# Expanders.net
KiCad netlist of a schematic drawn in Altium Designer
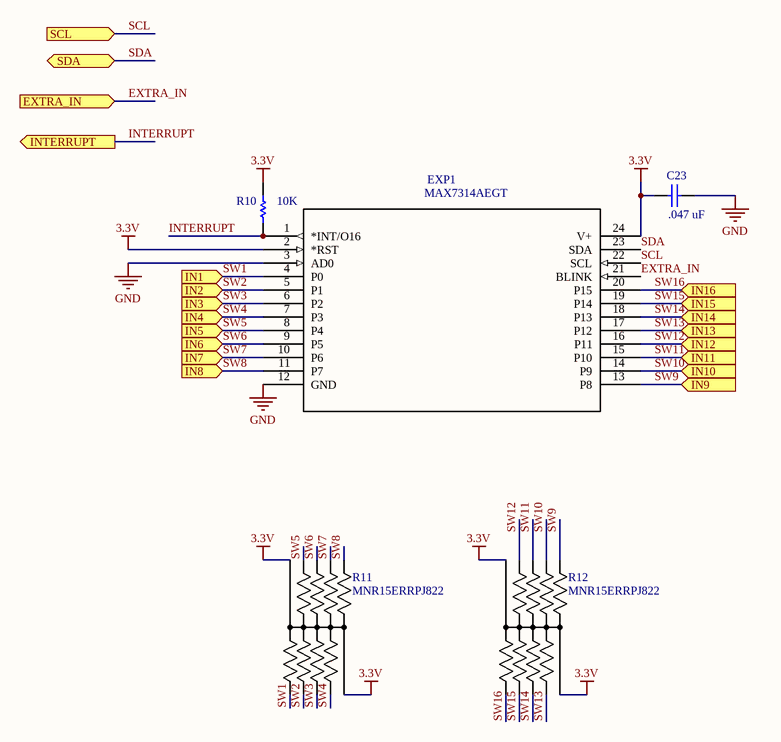
[diagram p0: Expanders.SchDoc]

(export (version "E")
  (design (tool "Eeschema 10.0.6"))
  (components
    (comp (ref "C23")
      (value ".047 uF")
      (footprint "RAD-0.1")
      (description "Capacitor")
      (fields (field (name "Comment") "Cap") (field (name "PUBLISHER") "Altium Limited"))
      (libsource (lib "Miscellaneous Devices") (part "Cap"))
    )
    (comp (ref "EXP1")
      (value "MAX7314AEGT")
      (footprint "21-0055H_24")
      (description "Interface IC - I/O extensions Maxim Integrated MAX7314AEG%2B PWM I%C2%B2C 400 kHz QSOP 24")
      (fields (field (name "MP") "MAX7314AEG+") (field (name "MF") "Maxim Integrated"))
      (libsource (lib "MAX7314AEGT") (part "MAX7314AEGT"))
    )
    (comp (ref "R10")
      (value "10K")
      (footprint "6-0805_N")
      (description "Resistor")
      (fields (field (name "Comment") "R5") (field (name "PUBLISHER") "Altium Limited"))
      (libsource (lib "Miscellaneous Devices") (part "Res1"))
    )
    (comp (ref "R11")
      (value "MNR15ERRPJ822")
      (footprint "MNR15")
      (description "Imported")
      (libsource (lib "surfacemountresarray") (part "MNR15ERRPJ822"))
    )
    (comp (ref "R12")
      (value "MNR15ERRPJ822")
      (footprint "MNR15")
      (description "Imported")
      (libsource (lib "surfacemountresarray") (part "MNR15ERRPJ822"))
    )
  )
  (nets
    (net (code "1") (name "/EXTRA_IN") (class "Default")
      (node (ref "EXP1") (pin "21") (pinfunction "BLINK_21") (pintype "input"))
    )
    (net (code "2") (name "/INTERRUPT") (class "Default")
      (node (ref "EXP1") (pin "1") (pinfunction "*INT/O16_1") (pintype "output"))
      (node (ref "R10") (pin "1") (pinfunction "1_1") (pintype "passive"))
    )
    (net (code "3") (name "/SCL") (class "Default")
      (node (ref "EXP1") (pin "22") (pinfunction "SCL_22") (pintype "input"))
    )
    (net (code "4") (name "/SDA") (class "Default")
      (node (ref "EXP1") (pin "23") (pinfunction "SDA_23") (pintype "passive"))
    )
    (net (code "5") (name "/SW1") (class "Default")
      (node (ref "EXP1") (pin "4") (pinfunction "P0_4") (pintype "passive"))
      (node (ref "R11") (pin "1") (pinfunction "1_1") (pintype "passive"))
    )
    (net (code "6") (name "/SW2") (class "Default")
      (node (ref "EXP1") (pin "5") (pinfunction "P1_5") (pintype "passive"))
      (node (ref "R11") (pin "2") (pinfunction "2_2") (pintype "passive"))
    )
    (net (code "7") (name "/SW3") (class "Default")
      (node (ref "EXP1") (pin "6") (pinfunction "P2_6") (pintype "passive"))
      (node (ref "R11") (pin "3") (pinfunction "3_3") (pintype "passive"))
    )
    (net (code "8") (name "/SW4") (class "Default")
      (node (ref "EXP1") (pin "7") (pinfunction "P3_7") (pintype "passive"))
      (node (ref "R11") (pin "4") (pinfunction "4_4") (pintype "passive"))
    )
    (net (code "9") (name "/SW5") (class "Default")
      (node (ref "EXP1") (pin "8") (pinfunction "P4_8") (pintype "passive"))
      (node (ref "R11") (pin "9") (pinfunction "9_9") (pintype "passive"))
    )
    (net (code "10") (name "/SW6") (class "Default")
      (node (ref "EXP1") (pin "9") (pinfunction "P5_9") (pintype "passive"))
      (node (ref "R11") (pin "8") (pinfunction "8_8") (pintype "passive"))
    )
    (net (code "11") (name "/SW7") (class "Default")
      (node (ref "EXP1") (pin "10") (pinfunction "P6_10") (pintype "passive"))
      (node (ref "R11") (pin "7") (pinfunction "7_7") (pintype "passive"))
    )
    (net (code "12") (name "/SW8") (class "Default")
      (node (ref "EXP1") (pin "11") (pinfunction "P7_11") (pintype "passive"))
      (node (ref "R11") (pin "6") (pinfunction "6_6") (pintype "passive"))
    )
    (net (code "13") (name "/SW9") (class "Default")
      (node (ref "EXP1") (pin "13") (pinfunction "P8_13") (pintype "passive"))
      (node (ref "R12") (pin "6") (pinfunction "6_6") (pintype "passive"))
    )
    (net (code "14") (name "/SW10") (class "Default")
      (node (ref "EXP1") (pin "14") (pinfunction "P9_14") (pintype "passive"))
      (node (ref "R12") (pin "7") (pinfunction "7_7") (pintype "passive"))
    )
    (net (code "15") (name "/SW11") (class "Default")
      (node (ref "EXP1") (pin "15") (pinfunction "P10_15") (pintype "passive"))
      (node (ref "R12") (pin "8") (pinfunction "8_8") (pintype "passive"))
    )
    (net (code "16") (name "/SW12") (class "Default")
      (node (ref "EXP1") (pin "16") (pinfunction "P11_16") (pintype "passive"))
      (node (ref "R12") (pin "9") (pinfunction "9_9") (pintype "passive"))
    )
    (net (code "17") (name "/SW13") (class "Default")
      (node (ref "EXP1") (pin "17") (pinfunction "P12_17") (pintype "passive"))
      (node (ref "R12") (pin "4") (pinfunction "4_4") (pintype "passive"))
    )
    (net (code "18") (name "/SW14") (class "Default")
      (node (ref "EXP1") (pin "18") (pinfunction "P13_18") (pintype "passive"))
      (node (ref "R12") (pin "3") (pinfunction "3_3") (pintype "passive"))
    )
    (net (code "19") (name "/SW15") (class "Default")
      (node (ref "EXP1") (pin "19") (pinfunction "P14_19") (pintype "passive"))
      (node (ref "R12") (pin "2") (pinfunction "2_2") (pintype "passive"))
    )
    (net (code "20") (name "/SW16") (class "Default")
      (node (ref "EXP1") (pin "20") (pinfunction "P15_20") (pintype "passive"))
      (node (ref "R12") (pin "1") (pinfunction "1_1") (pintype "passive"))
    )
    (net (code "21") (name "3.3V") (class "Default")
      (node (ref "C23") (pin "1") (pinfunction "1_1") (pintype "passive"))
      (node (ref "EXP1") (pin "2") (pinfunction "*RST_2") (pintype "input"))
      (node (ref "EXP1") (pin "24") (pinfunction "V+_24") (pintype "power_in"))
      (node (ref "R10") (pin "2") (pinfunction "2_2") (pintype "passive"))
      (node (ref "R11") (pin "10") (pinfunction "10_10") (pintype "passive"))
      (node (ref "R11") (pin "5") (pinfunction "5_5") (pintype "passive"))
      (node (ref "R12") (pin "10") (pinfunction "10_10") (pintype "passive"))
      (node (ref "R12") (pin "5") (pinfunction "5_5") (pintype "passive"))
    )
    (net (code "22") (name "GND") (class "Default")
      (node (ref "C23") (pin "2") (pinfunction "2_2") (pintype "passive"))
      (node (ref "EXP1") (pin "12") (pinfunction "GND_12") (pintype "power_in"))
      (node (ref "EXP1") (pin "3") (pinfunction "AD0_3") (pintype "input"))
    )
  )
)
